# BMS_schematic.net
KiCad netlist of a schematic drawn in Altium Designer
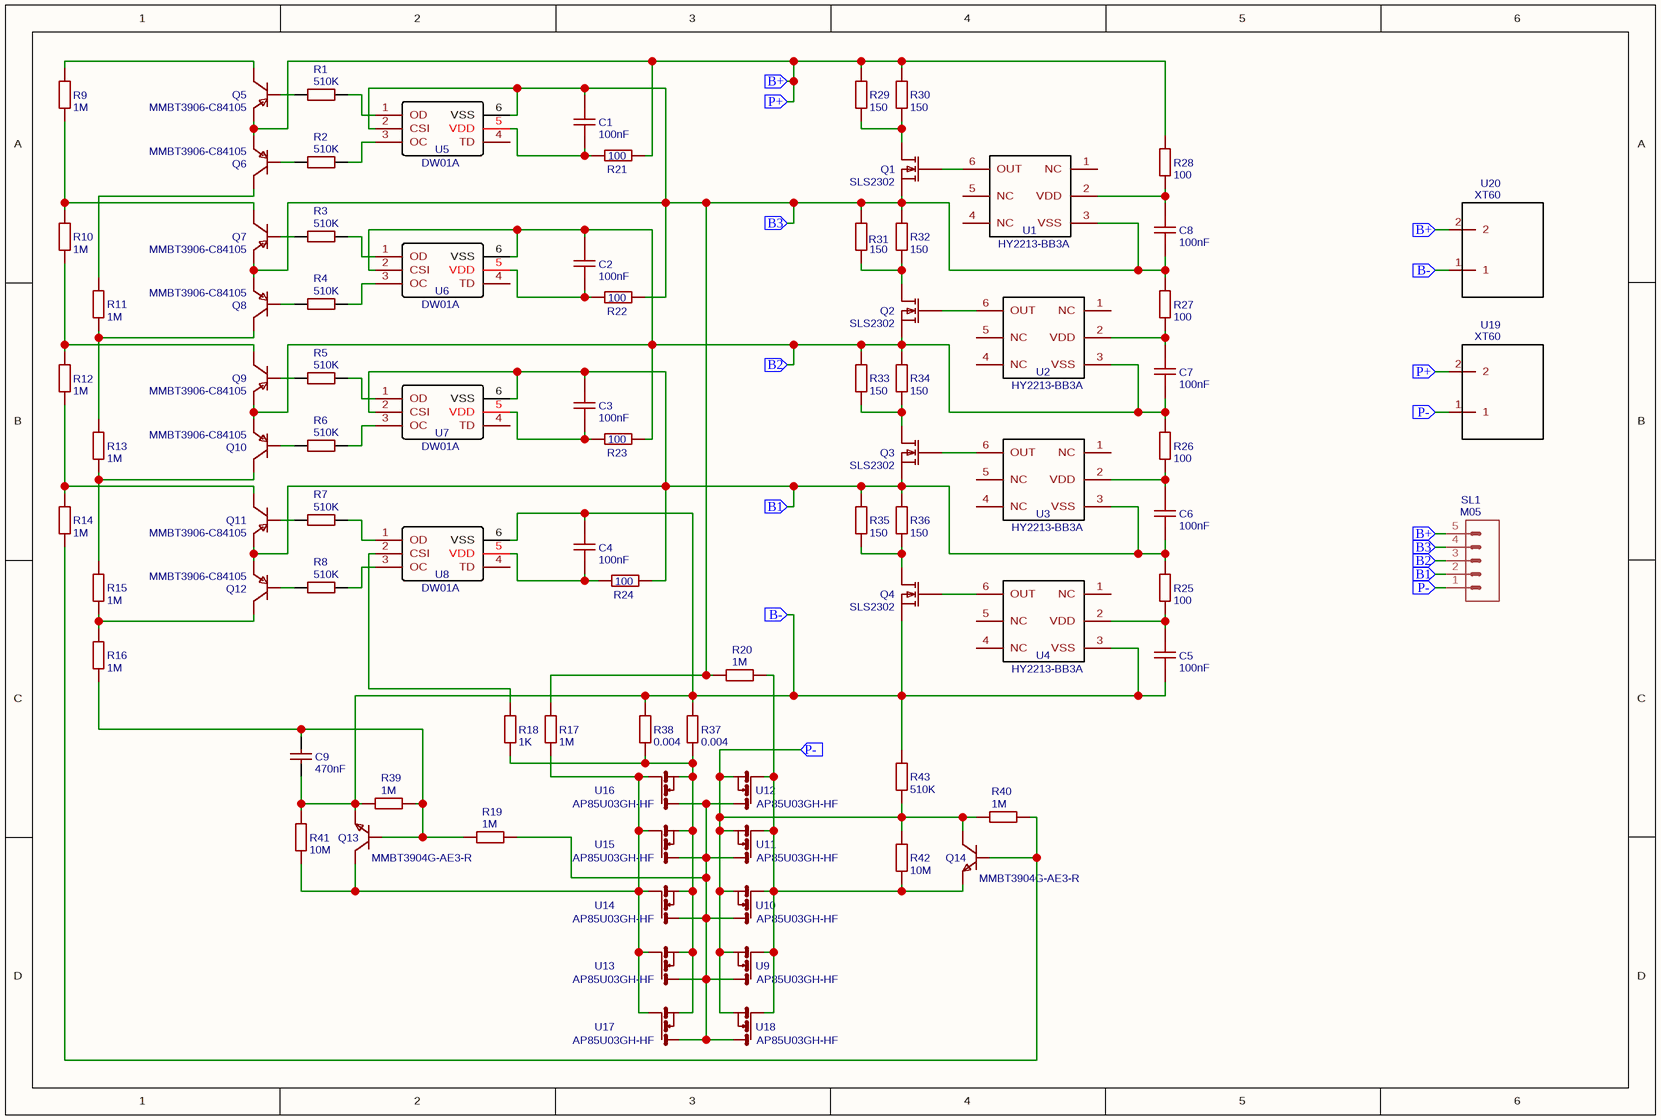
[diagram p0: BMS schematic.schdoc]

(export (version "E")
  (design (tool "Eeschema 10.0.6"))
  (components
    (comp (ref "C1")
      (value "100nF")
      (fields
        (field (name "BOM_SUPPLIER PART") "C495959")
        (field (name "BOM_MANUFACTURER PART") "C0805X104K101TB")
        (field (name "CONTRIBUTOR") "LCSC")
      )
      (libsource (lib "altium-import") (part "root_1_100nF_"))
    )
    (comp (ref "C2")
      (value "100nF")
      (fields
        (field (name "BOM_SUPPLIER PART") "C495959")
        (field (name "BOM_MANUFACTURER PART") "C0805X104K101TB")
        (field (name "CONTRIBUTOR") "LCSC")
      )
      (libsource (lib "altium-import") (part "root_1_100nF_"))
    )
    (comp (ref "C3")
      (value "100nF")
      (fields
        (field (name "BOM_SUPPLIER PART") "C495959")
        (field (name "BOM_MANUFACTURER PART") "C0805X104K101TB")
        (field (name "CONTRIBUTOR") "LCSC")
      )
      (libsource (lib "altium-import") (part "root_1_100nF_"))
    )
    (comp (ref "C4")
      (value "100nF")
      (fields
        (field (name "BOM_SUPPLIER PART") "C495959")
        (field (name "BOM_MANUFACTURER PART") "C0805X104K101TB")
        (field (name "CONTRIBUTOR") "LCSC")
      )
      (libsource (lib "altium-import") (part "root_1_100nF_"))
    )
    (comp (ref "C5")
      (value "100nF")
      (fields
        (field (name "BOM_SUPPLIER PART") "C495959")
        (field (name "BOM_MANUFACTURER PART") "C0805X104K101TB")
        (field (name "CONTRIBUTOR") "LCSC")
      )
      (libsource (lib "altium-import") (part "root_1_100nF_"))
    )
    (comp (ref "C6")
      (value "100nF")
      (fields
        (field (name "BOM_SUPPLIER PART") "C495959")
        (field (name "BOM_MANUFACTURER PART") "C0805X104K101TB")
        (field (name "CONTRIBUTOR") "LCSC")
      )
      (libsource (lib "altium-import") (part "root_1_100nF_"))
    )
    (comp (ref "C7")
      (value "100nF")
      (fields
        (field (name "BOM_SUPPLIER PART") "C495959")
        (field (name "BOM_MANUFACTURER PART") "C0805X104K101TB")
        (field (name "CONTRIBUTOR") "LCSC")
      )
      (libsource (lib "altium-import") (part "root_1_100nF_"))
    )
    (comp (ref "C8")
      (value "100nF")
      (fields
        (field (name "BOM_SUPPLIER PART") "C495959")
        (field (name "BOM_MANUFACTURER PART") "C0805X104K101TB")
        (field (name "CONTRIBUTOR") "LCSC")
      )
      (libsource (lib "altium-import") (part "root_1_100nF_"))
    )
    (comp (ref "C9")
      (value "470nF")
      (fields
        (field (name "BOM_MANUFACTURER PART") "CL21B474KBFNNNE")
        (field (name "BOM_SUPPLIER PART") "C13967")
      )
      (libsource (lib "altium-import") (part "root_3_470nF_"))
    )
    (comp (ref "Q1")
      (value "SLS2302")
      (fields (field (name "BOM_SUPPLIER PART") "C251150") (field (name "CONTRIBUTOR") "saidbek"))
      (libsource (lib "altium-import") (part "root_0_SLS2302_"))
    )
    (comp (ref "Q2")
      (value "SLS2302")
      (fields (field (name "BOM_SUPPLIER PART") "C251150") (field (name "CONTRIBUTOR") "saidbek"))
      (libsource (lib "altium-import") (part "root_0_SLS2302_"))
    )
    (comp (ref "Q3")
      (value "SLS2302")
      (fields (field (name "BOM_SUPPLIER PART") "C251150") (field (name "CONTRIBUTOR") "saidbek"))
      (libsource (lib "altium-import") (part "root_0_SLS2302_"))
    )
    (comp (ref "Q4")
      (value "SLS2302")
      (fields (field (name "BOM_SUPPLIER PART") "C251150") (field (name "CONTRIBUTOR") "saidbek"))
      (libsource (lib "altium-import") (part "root_0_SLS2302_"))
    )
    (comp (ref "Q5")
      (value "MMBT3906-C84105")
      (fields
        (field (name "BOM_MANUFACTURER PART") "MMBT3906")
        (field (name "BOM_SUPPLIER PART") "C84105")
        (field (name "CONTRIBUTOR") "立创EDA官方封装库")
      )
      (libsource (lib "altium-import") (part "root_0_MMBT3906-C84105_"))
    )
    (comp (ref "Q6")
      (value "MMBT3906-C84105")
      (fields
        (field (name "BOM_MANUFACTURER PART") "MMBT3906")
        (field (name "BOM_SUPPLIER PART") "C84105")
        (field (name "CONTRIBUTOR") "立创EDA官方封装库")
      )
      (libsource (lib "") (part "root_0_MMBT3906-C84105__1"))
    )
    (comp (ref "Q7")
      (value "MMBT3906-C84105")
      (fields
        (field (name "BOM_MANUFACTURER PART") "MMBT3906")
        (field (name "BOM_SUPPLIER PART") "C84105")
        (field (name "CONTRIBUTOR") "立创EDA官方封装库")
      )
      (libsource (lib "altium-import") (part "root_0_MMBT3906-C84105_"))
    )
    (comp (ref "Q8")
      (value "MMBT3906-C84105")
      (fields
        (field (name "BOM_MANUFACTURER PART") "MMBT3906")
        (field (name "BOM_SUPPLIER PART") "C84105")
        (field (name "CONTRIBUTOR") "立创EDA官方封装库")
      )
      (libsource (lib "") (part "root_0_MMBT3906-C84105__1"))
    )
    (comp (ref "Q9")
      (value "MMBT3906-C84105")
      (fields
        (field (name "BOM_MANUFACTURER PART") "MMBT3906")
        (field (name "BOM_SUPPLIER PART") "C84105")
        (field (name "CONTRIBUTOR") "立创EDA官方封装库")
      )
      (libsource (lib "altium-import") (part "root_0_MMBT3906-C84105_"))
    )
    (comp (ref "Q10")
      (value "MMBT3906-C84105")
      (fields
        (field (name "BOM_MANUFACTURER PART") "MMBT3906")
        (field (name "BOM_SUPPLIER PART") "C84105")
        (field (name "CONTRIBUTOR") "立创EDA官方封装库")
      )
      (libsource (lib "") (part "root_0_MMBT3906-C84105__1"))
    )
    (comp (ref "Q11")
      (value "MMBT3906-C84105")
      (fields
        (field (name "BOM_MANUFACTURER PART") "MMBT3906")
        (field (name "BOM_SUPPLIER PART") "C84105")
        (field (name "CONTRIBUTOR") "立创EDA官方封装库")
      )
      (libsource (lib "altium-import") (part "root_0_MMBT3906-C84105_"))
    )
    (comp (ref "Q12")
      (value "MMBT3906-C84105")
      (fields
        (field (name "BOM_MANUFACTURER PART") "MMBT3906")
        (field (name "BOM_SUPPLIER PART") "C84105")
        (field (name "CONTRIBUTOR") "立创EDA官方封装库")
      )
      (libsource (lib "") (part "root_0_MMBT3906-C84105__1"))
    )
    (comp (ref "Q13")
      (value "MMBT3904G-AE3-R")
      (fields (field (name "BOM_MANUFACTURER PART") "MMBT3904") (field (name "BOM_SUPPLIER PART") "C84104"))
      (libsource (lib "") (part "root_0_MMBT3904G-AE3-R__1"))
    )
    (comp (ref "Q14")
      (value "MMBT3904G-AE3-R")
      (fields (field (name "BOM_MANUFACTURER PART") "MMBT3904") (field (name "BOM_SUPPLIER PART") "C84104"))
      (libsource (lib "altium-import") (part "root_0_MMBT3904G-AE3-R_"))
    )
    (comp (ref "R1")
      (value "510K")
      (fields
        (field (name "BOM_MANUFACTURER PART") "RC0805JR-07510KL")
        (field (name "BOM_SUPPLIER PART") "C137422")
      )
      (libsource (lib "altium-import") (part "root_0_510K_"))
    )
    (comp (ref "R2")
      (value "510K")
      (fields
        (field (name "BOM_MANUFACTURER PART") "RC0805JR-07510KL")
        (field (name "BOM_SUPPLIER PART") "C137422")
      )
      (libsource (lib "altium-import") (part "root_0_510K_"))
    )
    (comp (ref "R3")
      (value "510K")
      (fields
        (field (name "BOM_MANUFACTURER PART") "RC0805JR-07510KL")
        (field (name "BOM_SUPPLIER PART") "C137422")
      )
      (libsource (lib "altium-import") (part "root_0_510K_"))
    )
    (comp (ref "R4")
      (value "510K")
      (fields
        (field (name "BOM_MANUFACTURER PART") "RC0805JR-07510KL")
        (field (name "BOM_SUPPLIER PART") "C137422")
      )
      (libsource (lib "altium-import") (part "root_0_510K_"))
    )
    (comp (ref "R5")
      (value "510K")
      (fields
        (field (name "BOM_MANUFACTURER PART") "RC0805JR-07510KL")
        (field (name "BOM_SUPPLIER PART") "C137422")
      )
      (libsource (lib "altium-import") (part "root_0_510K_"))
    )
    (comp (ref "R6")
      (value "510K")
      (fields
        (field (name "BOM_MANUFACTURER PART") "RC0805JR-07510KL")
        (field (name "BOM_SUPPLIER PART") "C137422")
      )
      (libsource (lib "altium-import") (part "root_0_510K_"))
    )
    (comp (ref "R7")
      (value "510K")
      (fields
        (field (name "BOM_MANUFACTURER PART") "RC0805JR-07510KL")
        (field (name "BOM_SUPPLIER PART") "C137422")
      )
      (libsource (lib "altium-import") (part "root_0_510K_"))
    )
    (comp (ref "R8")
      (value "510K")
      (fields
        (field (name "BOM_MANUFACTURER PART") "RC0805JR-07510KL")
        (field (name "BOM_SUPPLIER PART") "C137422")
      )
      (libsource (lib "altium-import") (part "root_0_510K_"))
    )
    (comp (ref "R9")
      (value "1M")
      (fields
        (field (name "BOM_SUPPLIER PART") "C325768")
        (field (name "BOM_MANUFACTURER PART") "RMC08051M1%N")
        (field (name "CONTRIBUTOR") "LCSC")
      )
      (libsource (lib "altium-import") (part "root_1_1M_"))
    )
    (comp (ref "R10")
      (value "1M")
      (fields
        (field (name "BOM_SUPPLIER PART") "C325768")
        (field (name "BOM_MANUFACTURER PART") "RMC08051M1%N")
        (field (name "CONTRIBUTOR") "LCSC")
      )
      (libsource (lib "altium-import") (part "root_1_1M_"))
    )
    (comp (ref "R11")
      (value "1M")
      (fields
        (field (name "BOM_SUPPLIER PART") "C325768")
        (field (name "BOM_MANUFACTURER PART") "RMC08051M1%N")
        (field (name "CONTRIBUTOR") "LCSC")
      )
      (libsource (lib "altium-import") (part "root_1_1M_"))
    )
    (comp (ref "R12")
      (value "1M")
      (fields
        (field (name "BOM_SUPPLIER PART") "C325768")
        (field (name "BOM_MANUFACTURER PART") "RMC08051M1%N")
        (field (name "CONTRIBUTOR") "LCSC")
      )
      (libsource (lib "altium-import") (part "root_1_1M_"))
    )
    (comp (ref "R13")
      (value "1M")
      (fields
        (field (name "BOM_SUPPLIER PART") "C325768")
        (field (name "BOM_MANUFACTURER PART") "RMC08051M1%N")
        (field (name "CONTRIBUTOR") "LCSC")
      )
      (libsource (lib "altium-import") (part "root_1_1M_"))
    )
    (comp (ref "R14")
      (value "1M")
      (fields
        (field (name "BOM_SUPPLIER PART") "C325768")
        (field (name "BOM_MANUFACTURER PART") "RMC08051M1%N")
        (field (name "CONTRIBUTOR") "LCSC")
      )
      (libsource (lib "altium-import") (part "root_1_1M_"))
    )
    (comp (ref "R15")
      (value "1M")
      (fields
        (field (name "BOM_SUPPLIER PART") "C325768")
        (field (name "BOM_MANUFACTURER PART") "RMC08051M1%N")
        (field (name "CONTRIBUTOR") "LCSC")
      )
      (libsource (lib "altium-import") (part "root_1_1M_"))
    )
    (comp (ref "R16")
      (value "1M")
      (fields
        (field (name "BOM_SUPPLIER PART") "C325768")
        (field (name "BOM_MANUFACTURER PART") "RMC08051M1%N")
        (field (name "CONTRIBUTOR") "LCSC")
      )
      (libsource (lib "altium-import") (part "root_1_1M_"))
    )
    (comp (ref "R17")
      (value "1M")
      (fields
        (field (name "BOM_SUPPLIER PART") "C325768")
        (field (name "BOM_MANUFACTURER PART") "RMC08051M1%N")
        (field (name "CONTRIBUTOR") "LCSC")
      )
      (libsource (lib "altium-import") (part "root_1_1M_"))
    )
    (comp (ref "R18")
      (value "1K")
      (fields
        (field (name "BOM_SUPPLIER PART") "C186253")
        (field (name "BOM_MANUFACTURER PART") "RN73H2ATTD1001B25")
        (field (name "CONTRIBUTOR") "LCSC")
      )
      (libsource (lib "altium-import") (part "root_1_1K_"))
    )
    (comp (ref "R19")
      (value "1M")
      (fields
        (field (name "BOM_SUPPLIER PART") "C325768")
        (field (name "BOM_MANUFACTURER PART") "RMC08051M1%N")
        (field (name "CONTRIBUTOR") "LCSC")
      )
      (libsource (lib "altium-import") (part "root_2_1M_"))
    )
    (comp (ref "R20")
      (value "1M")
      (fields
        (field (name "BOM_SUPPLIER PART") "C325768")
        (field (name "BOM_MANUFACTURER PART") "RMC08051M1%N")
        (field (name "CONTRIBUTOR") "LCSC")
      )
      (libsource (lib "altium-import") (part "root_2_1M_"))
    )
    (comp (ref "R21")
      (value "100")
      (fields
        (field (name "BOM_SUPPLIER PART") "C144538")
        (field (name "BOM_MANUFACTURER PART") "AC0805JR-07100RL")
        (field (name "CONTRIBUTOR") "LCSC")
      )
      (libsource (lib "altium-import") (part "root_0_100_"))
    )
    (comp (ref "R22")
      (value "100")
      (fields
        (field (name "BOM_SUPPLIER PART") "C144538")
        (field (name "BOM_MANUFACTURER PART") "AC0805JR-07100RL")
        (field (name "CONTRIBUTOR") "LCSC")
      )
      (libsource (lib "altium-import") (part "root_0_100_"))
    )
    (comp (ref "R23")
      (value "100")
      (fields
        (field (name "BOM_SUPPLIER PART") "C144538")
        (field (name "BOM_MANUFACTURER PART") "AC0805JR-07100RL")
        (field (name "CONTRIBUTOR") "LCSC")
      )
      (libsource (lib "altium-import") (part "root_0_100_"))
    )
    (comp (ref "R24")
      (value "100")
      (fields
        (field (name "BOM_SUPPLIER PART") "C144538")
        (field (name "BOM_MANUFACTURER PART") "AC0805JR-07100RL")
        (field (name "CONTRIBUTOR") "LCSC")
      )
      (libsource (lib "altium-import") (part "root_0_100_"))
    )
    (comp (ref "R25")
      (value "100")
      (fields
        (field (name "BOM_SUPPLIER PART") "C144538")
        (field (name "BOM_MANUFACTURER PART") "AC0805JR-07100RL")
        (field (name "CONTRIBUTOR") "LCSC")
      )
      (libsource (lib "altium-import") (part "root_1_100_"))
    )
    (comp (ref "R26")
      (value "100")
      (fields
        (field (name "BOM_SUPPLIER PART") "C144538")
        (field (name "BOM_MANUFACTURER PART") "AC0805JR-07100RL")
        (field (name "CONTRIBUTOR") "LCSC")
      )
      (libsource (lib "altium-import") (part "root_1_100_"))
    )
    (comp (ref "R27")
      (value "100")
      (fields
        (field (name "BOM_SUPPLIER PART") "C144538")
        (field (name "BOM_MANUFACTURER PART") "AC0805JR-07100RL")
        (field (name "CONTRIBUTOR") "LCSC")
      )
      (libsource (lib "altium-import") (part "root_1_100_"))
    )
    (comp (ref "R28")
      (value "100")
      (fields
        (field (name "BOM_SUPPLIER PART") "C144538")
        (field (name "BOM_MANUFACTURER PART") "AC0805JR-07100RL")
        (field (name "CONTRIBUTOR") "LCSC")
      )
      (libsource (lib "altium-import") (part "root_1_100_"))
    )
    (comp (ref "R29")
      (value "150")
      (fields
        (field (name "BOM_SUPPLIER PART") "C237796")
        (field (name "BOM_MANUFACTURER PART") "RMCF0805JT150R")
        (field (name "CONTRIBUTOR") "LCSC")
      )
      (libsource (lib "altium-import") (part "root_1_150_"))
    )
    (comp (ref "R30")
      (value "150")
      (fields
        (field (name "BOM_SUPPLIER PART") "C237796")
        (field (name "BOM_MANUFACTURER PART") "RMCF0805JT150R")
        (field (name "CONTRIBUTOR") "LCSC")
      )
      (libsource (lib "altium-import") (part "root_1_150_"))
    )
    (comp (ref "R31")
      (value "150")
      (fields
        (field (name "BOM_SUPPLIER PART") "C237796")
        (field (name "BOM_MANUFACTURER PART") "RMCF0805JT150R")
        (field (name "CONTRIBUTOR") "LCSC")
      )
      (libsource (lib "altium-import") (part "root_1_150_"))
    )
    (comp (ref "R32")
      (value "150")
      (fields
        (field (name "BOM_SUPPLIER PART") "C237796")
        (field (name "BOM_MANUFACTURER PART") "RMCF0805JT150R")
        (field (name "CONTRIBUTOR") "LCSC")
      )
      (libsource (lib "altium-import") (part "root_1_150_"))
    )
    (comp (ref "R33")
      (value "150")
      (fields
        (field (name "BOM_SUPPLIER PART") "C237796")
        (field (name "BOM_MANUFACTURER PART") "RMCF0805JT150R")
        (field (name "CONTRIBUTOR") "LCSC")
      )
      (libsource (lib "altium-import") (part "root_1_150_"))
    )
    (comp (ref "R34")
      (value "150")
      (fields
        (field (name "BOM_SUPPLIER PART") "C237796")
        (field (name "BOM_MANUFACTURER PART") "RMCF0805JT150R")
        (field (name "CONTRIBUTOR") "LCSC")
      )
      (libsource (lib "altium-import") (part "root_1_150_"))
    )
    (comp (ref "R35")
      (value "150")
      (fields
        (field (name "BOM_SUPPLIER PART") "C237796")
        (field (name "BOM_MANUFACTURER PART") "RMCF0805JT150R")
        (field (name "CONTRIBUTOR") "LCSC")
      )
      (libsource (lib "altium-import") (part "root_1_150_"))
    )
    (comp (ref "R36")
      (value "150")
      (fields
        (field (name "BOM_SUPPLIER PART") "C237796")
        (field (name "BOM_MANUFACTURER PART") "RMCF0805JT150R")
        (field (name "CONTRIBUTOR") "LCSC")
      )
      (libsource (lib "altium-import") (part "root_1_150_"))
    )
    (comp (ref "R37")
      (value "0.004")
      (fields
        (field (name "BOM_SUPPLIER PART") "C76237")
        (field (name "BOM_MANUFACTURER PART") "MRF6432(2512)LR004FTS")
        (field (name "CONTRIBUTOR") "LCSC")
      )
      (libsource (lib "altium-import") (part "root_1_0.004_"))
    )
    (comp (ref "R38")
      (value "0.004")
      (fields
        (field (name "BOM_SUPPLIER PART") "C76237")
        (field (name "BOM_MANUFACTURER PART") "MRF6432(2512)LR004FTS")
        (field (name "CONTRIBUTOR") "LCSC")
      )
      (libsource (lib "altium-import") (part "root_1_0.004_"))
    )
    (comp (ref "R39")
      (value "1M")
      (fields
        (field (name "BOM_SUPPLIER PART") "C325768")
        (field (name "BOM_MANUFACTURER PART") "RMC08051M1%N")
        (field (name "CONTRIBUTOR") "LCSC")
      )
      (libsource (lib "altium-import") (part "root_2_1M_"))
    )
    (comp (ref "R40")
      (value "1M")
      (fields
        (field (name "BOM_SUPPLIER PART") "C325768")
        (field (name "BOM_MANUFACTURER PART") "RMC08051M1%N")
        (field (name "CONTRIBUTOR") "LCSC")
      )
      (libsource (lib "altium-import") (part "root_0_1M_"))
    )
    (comp (ref "R41")
      (value "10M")
      (fields
        (field (name "BOM_SUPPLIER PART") "C325949")
        (field (name "BOM_MANUFACTURER PART") "RMC080510M1%N")
        (field (name "CONTRIBUTOR") "LCSC")
      )
      (libsource (lib "altium-import") (part "root_1_10M_"))
    )
    (comp (ref "R42")
      (value "10M")
      (fields
        (field (name "BOM_SUPPLIER PART") "C325949")
        (field (name "BOM_MANUFACTURER PART") "RMC080510M1%N")
        (field (name "CONTRIBUTOR") "LCSC")
      )
      (libsource (lib "altium-import") (part "root_1_10M_"))
    )
    (comp (ref "R43")
      (value "510K")
      (fields
        (field (name "BOM_SUPPLIER PART") "C245345")
        (field (name "BOM_MANUFACTURER PART") "CR0805F510KP05")
        (field (name "CONTRIBUTOR") "LCSC")
      )
      (libsource (lib "altium-import") (part "root_1_510K_"))
    )
    (comp (ref "SL1")
      (value "M05")
      (fields (field (name "CONTRIBUTOR") "sebby"))
      (libsource (lib "altium-import") (part "root_0_M05_"))
    )
    (comp (ref "U1")
      (value "HY2213-BB3A")
      (fields (field (name "BOM_SUPPLIER PART") "C113632"))
      (libsource (lib "altium-import") (part "root_0_HY2213-BB3A_"))
    )
    (comp (ref "U2")
      (value "HY2213-BB3A")
      (fields (field (name "BOM_SUPPLIER PART") "C113632"))
      (libsource (lib "altium-import") (part "root_0_HY2213-BB3A_"))
    )
    (comp (ref "U3")
      (value "HY2213-BB3A")
      (fields (field (name "BOM_SUPPLIER PART") "C113632"))
      (libsource (lib "altium-import") (part "root_0_HY2213-BB3A_"))
    )
    (comp (ref "U4")
      (value "HY2213-BB3A")
      (fields (field (name "BOM_SUPPLIER PART") "C113632"))
      (libsource (lib "altium-import") (part "root_0_HY2213-BB3A_"))
    )
    (comp (ref "U5")
      (value "DW01A")
      (fields (field (name "BOM_SUPPLIER PART") "C85680"))
      (libsource (lib "altium-import") (part "root_0_DW01A_"))
    )
    (comp (ref "U6")
      (value "DW01A")
      (fields (field (name "BOM_SUPPLIER PART") "C85680"))
      (libsource (lib "altium-import") (part "root_0_DW01A_"))
    )
    (comp (ref "U7")
      (value "DW01A")
      (fields (field (name "BOM_SUPPLIER PART") "C85680"))
      (libsource (lib "altium-import") (part "root_0_DW01A_"))
    )
    (comp (ref "U8")
      (value "DW01A")
      (fields (field (name "BOM_SUPPLIER PART") "C85680"))
      (libsource (lib "altium-import") (part "root_0_DW01A_"))
    )
    (comp (ref "U9")
      (value "AP85U03GH-HF")
      (fields
        (field (name "BOM_MANUFACTURER PART") "NCE3080K")
        (field (name "BOM_SUPPLIER PART") "C108901")
        (field (name "CONTRIBUTOR") "Jesseprominer")
      )
      (libsource (lib "altium-import") (part "root_0_AP85U03GH-HF_"))
    )
    (comp (ref "U10")
      (value "AP85U03GH-HF")
      (fields
        (field (name "BOM_MANUFACTURER PART") "NCE3080K")
        (field (name "BOM_SUPPLIER PART") "C108901")
        (field (name "CONTRIBUTOR") "Jesseprominer")
      )
      (libsource (lib "altium-import") (part "root_0_AP85U03GH-HF_"))
    )
    (comp (ref "U11")
      (value "AP85U03GH-HF")
      (fields
        (field (name "BOM_MANUFACTURER PART") "NCE3080K")
        (field (name "BOM_SUPPLIER PART") "C108901")
        (field (name "CONTRIBUTOR") "Jesseprominer")
      )
      (libsource (lib "altium-import") (part "root_0_AP85U03GH-HF_"))
    )
    (comp (ref "U12")
      (value "AP85U03GH-HF")
      (fields
        (field (name "BOM_MANUFACTURER PART") "NCE3080K")
        (field (name "BOM_SUPPLIER PART") "C108901")
        (field (name "CONTRIBUTOR") "Jesseprominer")
      )
      (libsource (lib "altium-import") (part "root_0_AP85U03GH-HF_"))
    )
    (comp (ref "U13")
      (value "AP85U03GH-HF")
      (fields
        (field (name "BOM_MANUFACTURER PART") "NCE3080K")
        (field (name "BOM_SUPPLIER PART") "C108901")
        (field (name "CONTRIBUTOR") "Jesseprominer")
      )
      (libsource (lib "") (part "root_0_AP85U03GH-HF__1"))
    )
    (comp (ref "U14")
      (value "AP85U03GH-HF")
      (fields
        (field (name "BOM_MANUFACTURER PART") "NCE3080K")
        (field (name "BOM_SUPPLIER PART") "C108901")
        (field (name "CONTRIBUTOR") "Jesseprominer")
      )
      (libsource (lib "") (part "root_0_AP85U03GH-HF__1"))
    )
    (comp (ref "U15")
      (value "AP85U03GH-HF")
      (fields
        (field (name "BOM_MANUFACTURER PART") "NCE3080K")
        (field (name "BOM_SUPPLIER PART") "C108901")
        (field (name "CONTRIBUTOR") "Jesseprominer")
      )
      (libsource (lib "") (part "root_0_AP85U03GH-HF__1"))
    )
    (comp (ref "U16")
      (value "AP85U03GH-HF")
      (fields
        (field (name "BOM_MANUFACTURER PART") "NCE3080K")
        (field (name "BOM_SUPPLIER PART") "C108901")
        (field (name "CONTRIBUTOR") "Jesseprominer")
      )
      (libsource (lib "") (part "root_0_AP85U03GH-HF__1"))
    )
    (comp (ref "U17")
      (value "AP85U03GH-HF")
      (fields
        (field (name "BOM_MANUFACTURER PART") "NCE3080K")
        (field (name "BOM_SUPPLIER PART") "C108901")
        (field (name "CONTRIBUTOR") "Jesseprominer")
      )
      (libsource (lib "") (part "root_0_AP85U03GH-HF__1"))
    )
    (comp (ref "U18")
      (value "AP85U03GH-HF")
      (fields
        (field (name "BOM_MANUFACTURER PART") "NCE3080K")
        (field (name "BOM_SUPPLIER PART") "C108901")
        (field (name "CONTRIBUTOR") "Jesseprominer")
      )
      (libsource (lib "altium-import") (part "root_0_AP85U03GH-HF_"))
    )
    (comp (ref "U19")
      (value "XT60")
      (fields (field (name "BOM_MANUFACTURER PART") "?") (field (name "CONTRIBUTOR") "Drone_H2EA"))
      (libsource (lib "altium-import") (part "root_2_XT60_"))
    )
    (comp (ref "U20")
      (value "XT60")
      (fields (field (name "BOM_MANUFACTURER PART") "?") (field (name "CONTRIBUTOR") "Drone_H2EA"))
      (libsource (lib "altium-import") (part "root_2_XT60_"))
    )
  )
  (nets
    (net (code "1") (name "/B+") (class "Default")
      (node (ref "Q5") (pin "2") (pinfunction "E_2") (pintype "passive"))
      (node (ref "Q6") (pin "2") (pinfunction "E_2") (pintype "passive"))
      (node (ref "R21") (pin "2") (pinfunction "2_2") (pintype "passive"))
      (node (ref "R28") (pin "2") (pinfunction "2_2") (pintype "passive"))
      (node (ref "R29") (pin "2") (pinfunction "2_2") (pintype "passive"))
      (node (ref "R30") (pin "2") (pinfunction "2_2") (pintype "passive"))
      (node (ref "SL1") (pin "5") (pinfunction "5_5") (pintype "passive"))
      (node (ref "U19") (pin "2") (pinfunction "2_2") (pintype "passive"))
      (node (ref "U20") (pin "2") (pinfunction "2_2") (pintype "passive"))
    )
    (net (code "2") (name "/B-") (class "Default")
      (node (ref "C4") (pin "2") (pinfunction "2_2") (pintype "passive"))
      (node (ref "C5") (pin "1") (pinfunction "1_1") (pintype "passive"))
      (node (ref "C9") (pin "2") (pinfunction "2_2") (pintype "passive"))
      (node (ref "Q13") (pin "1") (pinfunction "E_1") (pintype "passive"))
      (node (ref "Q4") (pin "2") (pinfunction "S_2") (pintype "passive"))
      (node (ref "R37") (pin "2") (pinfunction "2_2") (pintype "passive"))
      (node (ref "R38") (pin "2") (pinfunction "2_2") (pintype "passive"))
      (node (ref "R39") (pin "2") (pinfunction "2_2") (pintype "passive"))
      (node (ref "R41") (pin "2") (pinfunction "2_2") (pintype "passive"))
      (node (ref "R43") (pin "2") (pinfunction "2_2") (pintype "passive"))
      (node (ref "U20") (pin "1") (pinfunction "1_1") (pintype "passive"))
      (node (ref "U4") (pin "3") (pinfunction "VSS_3") (pintype "passive"))
      (node (ref "U8") (pin "6") (pinfunction "VSS_6") (pintype "passive"))
    )
    (net (code "3") (name "/B1") (class "Default")
      (node (ref "C3") (pin "2") (pinfunction "2_2") (pintype "passive"))
      (node (ref "C6") (pin "1") (pinfunction "1_1") (pintype "passive"))
      (node (ref "Q11") (pin "2") (pinfunction "E_2") (pintype "passive"))
      (node (ref "Q12") (pin "2") (pinfunction "E_2") (pintype "passive"))
      (node (ref "Q3") (pin "2") (pinfunction "S_2") (pintype "passive"))
      (node (ref "R24") (pin "2") (pinfunction "2_2") (pintype "passive"))
      (node (ref "R25") (pin "2") (pinfunction "2_2") (pintype "passive"))
      (node (ref "R35") (pin "2") (pinfunction "2_2") (pintype "passive"))
      (node (ref "R36") (pin "2") (pinfunction "2_2") (pintype "passive"))
      (node (ref "SL1") (pin "2") (pinfunction "2_2") (pintype "passive"))
      (node (ref "U3") (pin "3") (pinfunction "VSS_3") (pintype "passive"))
      (node (ref "U7") (pin "2") (pinfunction "CSI_2") (pintype "passive"))
      (node (ref "U7") (pin "6") (pinfunction "VSS_6") (pintype "passive"))
    )
    (net (code "4") (name "/B2") (class "Default")
      (node (ref "C2") (pin "2") (pinfunction "2_2") (pintype "passive"))
      (node (ref "C7") (pin "1") (pinfunction "1_1") (pintype "passive"))
      (node (ref "Q10") (pin "2") (pinfunction "E_2") (pintype "passive"))
      (node (ref "Q2") (pin "2") (pinfunction "S_2") (pintype "passive"))
      (node (ref "Q9") (pin "2") (pinfunction "E_2") (pintype "passive"))
      (node (ref "R23") (pin "2") (pinfunction "2_2") (pintype "passive"))
      (node (ref "R26") (pin "2") (pinfunction "2_2") (pintype "passive"))
      (node (ref "R33") (pin "2") (pinfunction "2_2") (pintype "passive"))
      (node (ref "R34") (pin "2") (pinfunction "2_2") (pintype "passive"))
      (node (ref "SL1") (pin "3") (pinfunction "3_3") (pintype "passive"))
      (node (ref "U2") (pin "3") (pinfunction "VSS_3") (pintype "passive"))
      (node (ref "U6") (pin "2") (pinfunction "CSI_2") (pintype "passive"))
      (node (ref "U6") (pin "6") (pinfunction "VSS_6") (pintype "passive"))
    )
    (net (code "5") (name "/B3") (class "Default")
      (node (ref "C1") (pin "2") (pinfunction "2_2") (pintype "passive"))
      (node (ref "C8") (pin "1") (pinfunction "1_1") (pintype "passive"))
      (node (ref "Q1") (pin "2") (pinfunction "S_2") (pintype "passive"))
      (node (ref "Q7") (pin "2") (pinfunction "E_2") (pintype "passive"))
      (node (ref "Q8") (pin "2") (pinfunction "E_2") (pintype "passive"))
      (node (ref "R17") (pin "2") (pinfunction "2_2") (pintype "passive"))
      (node (ref "R20") (pin "2") (pinfunction "2_2") (pintype "passive"))
      (node (ref "R22") (pin "2") (pinfunction "2_2") (pintype "passive"))
      (node (ref "R27") (pin "2") (pinfunction "2_2") (pintype "passive"))
      (node (ref "R31") (pin "2") (pinfunction "2_2") (pintype "passive"))
      (node (ref "R32") (pin "2") (pinfunction "2_2") (pintype "passive"))
      (node (ref "SL1") (pin "4") (pinfunction "4_4") (pintype "passive"))
      (node (ref "U1") (pin "3") (pinfunction "VSS_3") (pintype "passive"))
      (node (ref "U5") (pin "2") (pinfunction "CSI_2") (pintype "passive"))
      (node (ref "U5") (pin "6") (pinfunction "VSS_6") (pintype "passive"))
    )
    (net (code "6") (name "/P-") (class "Default")
      (node (ref "Q14") (pin "3") (pinfunction "C_3") (pintype "passive"))
      (node (ref "R40") (pin "1") (pinfunction "1_1") (pintype "passive"))
      (node (ref "R42") (pin "2") (pinfunction "2_2") (pintype "passive"))
      (node (ref "R43") (pin "1") (pinfunction "1_1") (pintype "passive"))
      (node (ref "SL1") (pin "1") (pinfunction "1_1") (pintype "passive"))
      (node (ref "U10") (pin "3") (pinfunction "S_3") (pintype "passive"))
      (node (ref "U11") (pin "3") (pinfunction "S_3") (pintype "passive"))
      (node (ref "U12") (pin "3") (pinfunction "S_3") (pintype "passive"))
      (node (ref "U18") (pin "3") (pinfunction "S_3") (pintype "passive"))
      (node (ref "U19") (pin "1") (pinfunction "1_1") (pintype "passive"))
      (node (ref "U9") (pin "3") (pinfunction "S_3") (pintype "passive"))
    )
    (net (code "7") (name "Net-(Q1-D)") (class "Default")
      (node (ref "Q1") (pin "3") (pinfunction "D_3") (pintype "passive"))
      (node (ref "R29") (pin "1") (pinfunction "1_1") (pintype "passive"))
      (node (ref "R30") (pin "1") (pinfunction "1_1") (pintype "passive"))
    )
    (net (code "8") (name "Net-(Q1-G)") (class "Default")
      (node (ref "Q1") (pin "1") (pinfunction "G_1") (pintype "passive"))
      (node (ref "U1") (pin "6") (pinfunction "OUT_6") (pintype "passive"))
    )
    (net (code "9") (name "Net-(Q2-D)") (class "Default")
      (node (ref "Q2") (pin "3") (pinfunction "D_3") (pintype "passive"))
      (node (ref "R31") (pin "1") (pinfunction "1_1") (pintype "passive"))
      (node (ref "R32") (pin "1") (pinfunction "1_1") (pintype "passive"))
    )
    (net (code "10") (name "Net-(Q2-G)") (class "Default")
      (node (ref "Q2") (pin "1") (pinfunction "G_1") (pintype "passive"))
      (node (ref "U2") (pin "6") (pinfunction "OUT_6") (pintype "passive"))
    )
    (net (code "11") (name "Net-(Q3-D)") (class "Default")
      (node (ref "Q3") (pin "3") (pinfunction "D_3") (pintype "passive"))
      (node (ref "R33") (pin "1") (pinfunction "1_1") (pintype "passive"))
      (node (ref "R34") (pin "1") (pinfunction "1_1") (pintype "passive"))
    )
    (net (code "12") (name "Net-(Q3-G)") (class "Default")
      (node (ref "Q3") (pin "1") (pinfunction "G_1") (pintype "passive"))
      (node (ref "U3") (pin "6") (pinfunction "OUT_6") (pintype "passive"))
    )
    (net (code "13") (name "Net-(Q4-D)") (class "Default")
      (node (ref "Q4") (pin "3") (pinfunction "D_3") (pintype "passive"))
      (node (ref "R35") (pin "1") (pinfunction "1_1") (pintype "passive"))
      (node (ref "R36") (pin "1") (pinfunction "1_1") (pintype "passive"))
    )
    (net (code "14") (name "Net-(Q4-G)") (class "Default")
      (node (ref "Q4") (pin "1") (pinfunction "G_1") (pintype "passive"))
      (node (ref "U4") (pin "6") (pinfunction "OUT_6") (pintype "passive"))
    )
    (net (code "15") (name "Net-(Q5-B)") (class "Default")
      (node (ref "Q5") (pin "1") (pinfunction "B_1") (pintype "passive"))
      (node (ref "R1") (pin "1") (pinfunction "1_1") (pintype "passive"))
    )
    (net (code "16") (name "Net-(Q5-C)") (class "Default")
      (node (ref "Q5") (pin "3") (pinfunction "C_3") (pintype "passive"))
      (node (ref "R9") (pin "2") (pinfunction "2_2") (pintype "passive"))
    )
    (net (code "17") (name "Net-(Q6-B)") (class "Default")
      (node (ref "Q6") (pin "1") (pinfunction "B_1") (pintype "passive"))
      (node (ref "R2") (pin "1") (pinfunction "1_1") (pintype "passive"))
    )
    (net (code "18") (name "Net-(Q6-C)") (class "Default")
      (node (ref "Q6") (pin "3") (pinfunction "C_3") (pintype "passive"))
      (node (ref "R11") (pin "2") (pinfunction "2_2") (pintype "passive"))
    )
    (net (code "19") (name "Net-(Q7-B)") (class "Default")
      (node (ref "Q7") (pin "1") (pinfunction "B_1") (pintype "passive"))
      (node (ref "R3") (pin "1") (pinfunction "1_1") (pintype "passive"))
    )
    (net (code "20") (name "Net-(Q7-C)") (class "Default")
      (node (ref "Q7") (pin "3") (pinfunction "C_3") (pintype "passive"))
      (node (ref "R10") (pin "2") (pinfunction "2_2") (pintype "passive"))
      (node (ref "R9") (pin "1") (pinfunction "1_1") (pintype "passive"))
    )
    (net (code "21") (name "Net-(Q8-B)") (class "Default")
      (node (ref "Q8") (pin "1") (pinfunction "B_1") (pintype "passive"))
      (node (ref "R4") (pin "1") (pinfunction "1_1") (pintype "passive"))
    )
    (net (code "22") (name "Net-(Q8-C)") (class "Default")
      (node (ref "Q8") (pin "3") (pinfunction "C_3") (pintype "passive"))
      (node (ref "R11") (pin "1") (pinfunction "1_1") (pintype "passive"))
      (node (ref "R13") (pin "2") (pinfunction "2_2") (pintype "passive"))
    )
    (net (code "23") (name "Net-(Q9-B)") (class "Default")
      (node (ref "Q9") (pin "1") (pinfunction "B_1") (pintype "passive"))
      (node (ref "R5") (pin "1") (pinfunction "1_1") (pintype "passive"))
    )
    (net (code "24") (name "Net-(Q9-C)") (class "Default")
      (node (ref "Q9") (pin "3") (pinfunction "C_3") (pintype "passive"))
      (node (ref "R10") (pin "1") (pinfunction "1_1") (pintype "passive"))
      (node (ref "R12") (pin "2") (pinfunction "2_2") (pintype "passive"))
    )
    (net (code "25") (name "Net-(Q10-B)") (class "Default")
      (node (ref "Q10") (pin "1") (pinfunction "B_1") (pintype "passive"))
      (node (ref "R6") (pin "1") (pinfunction "1_1") (pintype "passive"))
    )
    (net (code "26") (name "Net-(Q10-C)") (class "Default")
      (node (ref "Q10") (pin "3") (pinfunction "C_3") (pintype "passive"))
      (node (ref "R13") (pin "1") (pinfunction "1_1") (pintype "passive"))
      (node (ref "R15") (pin "2") (pinfunction "2_2") (pintype "passive"))
    )
    (net (code "27") (name "Net-(Q11-B)") (class "Default")
      (node (ref "Q11") (pin "1") (pinfunction "B_1") (pintype "passive"))
      (node (ref "R7") (pin "1") (pinfunction "1_1") (pintype "passive"))
    )
    (net (code "28") (name "Net-(Q11-C)") (class "Default")
      (node (ref "Q11") (pin "3") (pinfunction "C_3") (pintype "passive"))
      (node (ref "R12") (pin "1") (pinfunction "1_1") (pintype "passive"))
      (node (ref "R14") (pin "2") (pinfunction "2_2") (pintype "passive"))
    )
    (net (code "29") (name "Net-(Q12-B)") (class "Default")
      (node (ref "Q12") (pin "1") (pinfunction "B_1") (pintype "passive"))
      (node (ref "R8") (pin "1") (pinfunction "1_1") (pintype "passive"))
    )
    (net (code "30") (name "Net-(Q12-C)") (class "Default")
      (node (ref "Q12") (pin "3") (pinfunction "C_3") (pintype "passive"))
      (node (ref "R15") (pin "1") (pinfunction "1_1") (pintype "passive"))
      (node (ref "R16") (pin "2") (pinfunction "2_2") (pintype "passive"))
    )
    (net (code "31") (name "Net-(Q13-B)") (class "Default")
      (node (ref "C9") (pin "1") (pinfunction "1_1") (pintype "passive"))
      (node (ref "Q13") (pin "2") (pinfunction "B_2") (pintype "passive"))
      (node (ref "R16") (pin "1") (pinfunction "1_1") (pintype "passive"))
      (node (ref "R19") (pin "2") (pinfunction "2_2") (pintype "passive"))
      (node (ref "R39") (pin "1") (pinfunction "1_1") (pintype "passive"))
    )
    (net (code "32") (name "Net-(Q13-C)") (class "Default")
      (node (ref "Q13") (pin "3") (pinfunction "C_3") (pintype "passive"))
      (node (ref "R17") (pin "1") (pinfunction "1_1") (pintype "passive"))
      (node (ref "R41") (pin "1") (pinfunction "1_1") (pintype "passive"))
      (node (ref "U13") (pin "1") (pinfunction "G_1") (pintype "passive"))
      (node (ref "U14") (pin "1") (pinfunction "G_1") (pintype "passive"))
      (node (ref "U15") (pin "1") (pinfunction "G_1") (pintype "passive"))
      (node (ref "U16") (pin "1") (pinfunction "G_1") (pintype "passive"))
      (node (ref "U17") (pin "1") (pinfunction "G_1") (pintype "passive"))
    )
    (net (code "33") (name "Net-(Q14-B)") (class "Default")
      (node (ref "Q14") (pin "2") (pinfunction "B_2") (pintype "passive"))
      (node (ref "R14") (pin "1") (pinfunction "1_1") (pintype "passive"))
      (node (ref "R40") (pin "2") (pinfunction "2_2") (pintype "passive"))
    )
    (net (code "34") (name "Net-(Q14-E)") (class "Default")
      (node (ref "Q14") (pin "1") (pinfunction "E_1") (pintype "passive"))
      (node (ref "R20") (pin "1") (pinfunction "1_1") (pintype "passive"))
      (node (ref "R42") (pin "1") (pinfunction "1_1") (pintype "passive"))
      (node (ref "U10") (pin "1") (pinfunction "G_1") (pintype "passive"))
      (node (ref "U11") (pin "1") (pinfunction "G_1") (pintype "passive"))
      (node (ref "U12") (pin "1") (pinfunction "G_1") (pintype "passive"))
      (node (ref "U18") (pin "1") (pinfunction "G_1") (pintype "passive"))
      (node (ref "U9") (pin "1") (pinfunction "G_1") (pintype "passive"))
    )
    (net (code "35") (name "Net-(U1-VDD)") (class "Default")
      (node (ref "C8") (pin "2") (pinfunction "2_2") (pintype "passive"))
      (node (ref "R28") (pin "1") (pinfunction "1_1") (pintype "passive"))
      (node (ref "U1") (pin "2") (pinfunction "VDD_2") (pintype "passive"))
    )
    (net (code "36") (name "Net-(U2-VDD)") (class "Default")
      (node (ref "C7") (pin "2") (pinfunction "2_2") (pintype "passive"))
      (node (ref "R27") (pin "1") (pinfunction "1_1") (pintype "passive"))
      (node (ref "U2") (pin "2") (pinfunction "VDD_2") (pintype "passive"))
    )
    (net (code "37") (name "Net-(U3-VDD)") (class "Default")
      (node (ref "C6") (pin "2") (pinfunction "2_2") (pintype "passive"))
      (node (ref "R26") (pin "1") (pinfunction "1_1") (pintype "passive"))
      (node (ref "U3") (pin "2") (pinfunction "VDD_2") (pintype "passive"))
    )
    (net (code "38") (name "Net-(U4-VDD)") (class "Default")
      (node (ref "C5") (pin "2") (pinfunction "2_2") (pintype "passive"))
      (node (ref "R25") (pin "1") (pinfunction "1_1") (pintype "passive"))
      (node (ref "U4") (pin "2") (pinfunction "VDD_2") (pintype "passive"))
    )
    (net (code "39") (name "Net-(U5-OC)") (class "Default")
      (node (ref "R2") (pin "2") (pinfunction "2_2") (pintype "passive"))
      (node (ref "U5") (pin "3") (pinfunction "OC_3") (pintype "passive"))
    )
    (net (code "40") (name "Net-(U5-OD)") (class "Default")
      (node (ref "R1") (pin "2") (pinfunction "2_2") (pintype "passive"))
      (node (ref "U5") (pin "1") (pinfunction "OD_1") (pintype "passive"))
    )
    (net (code "41") (name "Net-(U5-VDD)") (class "Default")
      (node (ref "C1") (pin "1") (pinfunction "1_1") (pintype "passive"))
      (node (ref "R21") (pin "1") (pinfunction "1_1") (pintype "passive"))
      (node (ref "U5") (pin "5") (pinfunction "VDD_5") (pintype "passive"))
    )
    (net (code "42") (name "Net-(U6-OC)") (class "Default")
      (node (ref "R4") (pin "2") (pinfunction "2_2") (pintype "passive"))
      (node (ref "U6") (pin "3") (pinfunction "OC_3") (pintype "passive"))
    )
    (net (code "43") (name "Net-(U6-OD)") (class "Default")
      (node (ref "R3") (pin "2") (pinfunction "2_2") (pintype "passive"))
      (node (ref "U6") (pin "1") (pinfunction "OD_1") (pintype "passive"))
    )
    (net (code "44") (name "Net-(U6-VDD)") (class "Default")
      (node (ref "C2") (pin "1") (pinfunction "1_1") (pintype "passive"))
      (node (ref "R22") (pin "1") (pinfunction "1_1") (pintype "passive"))
      (node (ref "U6") (pin "5") (pinfunction "VDD_5") (pintype "passive"))
    )
    (net (code "45") (name "Net-(U7-OC)") (class "Default")
      (node (ref "R6") (pin "2") (pinfunction "2_2") (pintype "passive"))
      (node (ref "U7") (pin "3") (pinfunction "OC_3") (pintype "passive"))
    )
    (net (code "46") (name "Net-(U7-OD)") (class "Default")
      (node (ref "R5") (pin "2") (pinfunction "2_2") (pintype "passive"))
      (node (ref "U7") (pin "1") (pinfunction "OD_1") (pintype "passive"))
    )
    (net (code "47") (name "Net-(U7-VDD)") (class "Default")
      (node (ref "C3") (pin "1") (pinfunction "1_1") (pintype "passive"))
      (node (ref "R23") (pin "1") (pinfunction "1_1") (pintype "passive"))
      (node (ref "U7") (pin "5") (pinfunction "VDD_5") (pintype "passive"))
    )
    (net (code "48") (name "Net-(U8-CSI)") (class "Default")
      (node (ref "R18") (pin "2") (pinfunction "2_2") (pintype "passive"))
      (node (ref "U8") (pin "2") (pinfunction "CSI_2") (pintype "passive"))
    )
    (net (code "49") (name "Net-(U8-OC)") (class "Default")
      (node (ref "R8") (pin "2") (pinfunction "2_2") (pintype "passive"))
      (node (ref "U8") (pin "3") (pinfunction "OC_3") (pintype "passive"))
    )
    (net (code "50") (name "Net-(U8-OD)") (class "Default")
      (node (ref "R7") (pin "2") (pinfunction "2_2") (pintype "passive"))
      (node (ref "U8") (pin "1") (pinfunction "OD_1") (pintype "passive"))
    )
    (net (code "51") (name "Net-(U8-VDD)") (class "Default")
      (node (ref "C4") (pin "1") (pinfunction "1_1") (pintype "passive"))
      (node (ref "R24") (pin "1") (pinfunction "1_1") (pintype "passive"))
      (node (ref "U8") (pin "5") (pinfunction "VDD_5") (pintype "passive"))
    )
    (net (code "52") (name "Net-(U10-D)") (class "Default")
      (node (ref "R19") (pin "1") (pinfunction "1_1") (pintype "passive"))
      (node (ref "U10") (pin "2") (pinfunction "D_2") (pintype "passive"))
      (node (ref "U11") (pin "2") (pinfunction "D_2") (pintype "passive"))
      (node (ref "U12") (pin "2") (pinfunction "D_2") (pintype "passive"))
      (node (ref "U13") (pin "2") (pinfunction "D_2") (pintype "passive"))
      (node (ref "U14") (pin "2") (pinfunction "D_2") (pintype "passive"))
      (node (ref "U15") (pin "2") (pinfunction "D_2") (pintype "passive"))
      (node (ref "U16") (pin "2") (pinfunction "D_2") (pintype "passive"))
      (node (ref "U17") (pin "2") (pinfunction "D_2") (pintype "passive"))
      (node (ref "U18") (pin "2") (pinfunction "D_2") (pintype "passive"))
      (node (ref "U9") (pin "2") (pinfunction "D_2") (pintype "passive"))
    )
    (net (code "53") (name "Net-(U13-S)") (class "Default")
      (node (ref "R18") (pin "1") (pinfunction "1_1") (pintype "passive"))
      (node (ref "R37") (pin "1") (pinfunction "1_1") (pintype "passive"))
      (node (ref "R38") (pin "1") (pinfunction "1_1") (pintype "passive"))
      (node (ref "U13") (pin "3") (pinfunction "S_3") (pintype "passive"))
      (node (ref "U14") (pin "3") (pinfunction "S_3") (pintype "passive"))
      (node (ref "U15") (pin "3") (pinfunction "S_3") (pintype "passive"))
      (node (ref "U16") (pin "3") (pinfunction "S_3") (pintype "passive"))
      (node (ref "U17") (pin "3") (pinfunction "S_3") (pintype "passive"))
    )
    (net (code "54") (name "unconnected-(U1-NC-Pad1)") (class "Default")
      (node (ref "U1") (pin "1") (pinfunction "NC_1") (pintype "passive"))
    )
    (net (code "55") (name "unconnected-(U1-NC-Pad4)") (class "Default")
      (node (ref "U1") (pin "4") (pinfunction "NC_4") (pintype "passive"))
    )
    (net (code "56") (name "unconnected-(U1-NC-Pad5)") (class "Default")
      (node (ref "U1") (pin "5") (pinfunction "NC_5") (pintype "passive"))
    )
    (net (code "57") (name "unconnected-(U2-NC-Pad1)") (class "Default")
      (node (ref "U2") (pin "1") (pinfunction "NC_1") (pintype "passive"))
    )
    (net (code "58") (name "unconnected-(U2-NC-Pad4)") (class "Default")
      (node (ref "U2") (pin "4") (pinfunction "NC_4") (pintype "passive"))
    )
    (net (code "59") (name "unconnected-(U2-NC-Pad5)") (class "Default")
      (node (ref "U2") (pin "5") (pinfunction "NC_5") (pintype "passive"))
    )
    (net (code "60") (name "unconnected-(U3-NC-Pad1)") (class "Default")
      (node (ref "U3") (pin "1") (pinfunction "NC_1") (pintype "passive"))
    )
    (net (code "61") (name "unconnected-(U3-NC-Pad4)") (class "Default")
      (node (ref "U3") (pin "4") (pinfunction "NC_4") (pintype "passive"))
    )
    (net (code "62") (name "unconnected-(U3-NC-Pad5)") (class "Default")
      (node (ref "U3") (pin "5") (pinfunction "NC_5") (pintype "passive"))
    )
    (net (code "63") (name "unconnected-(U4-NC-Pad1)") (class "Default")
      (node (ref "U4") (pin "1") (pinfunction "NC_1") (pintype "passive"))
    )
    (net (code "64") (name "unconnected-(U4-NC-Pad4)") (class "Default")
      (node (ref "U4") (pin "4") (pinfunction "NC_4") (pintype "passive"))
    )
    (net (code "65") (name "unconnected-(U4-NC-Pad5)") (class "Default")
      (node (ref "U4") (pin "5") (pinfunction "NC_5") (pintype "passive"))
    )
    (net (code "66") (name "unconnected-(U5-TD-Pad4)") (class "Default")
      (node (ref "U5") (pin "4") (pinfunction "TD_4") (pintype "passive"))
    )
    (net (code "67") (name "unconnected-(U6-TD-Pad4)") (class "Default")
      (node (ref "U6") (pin "4") (pinfunction "TD_4") (pintype "passive"))
    )
    (net (code "68") (name "unconnected-(U7-TD-Pad4)") (class "Default")
      (node (ref "U7") (pin "4") (pinfunction "TD_4") (pintype "passive"))
    )
    (net (code "69") (name "unconnected-(U8-TD-Pad4)") (class "Default")
      (node (ref "U8") (pin "4") (pinfunction "TD_4") (pintype "passive"))
    )
  )
)
